# Ampli-Mic.net
KiCad netlist of a schematic drawn in EAGLE
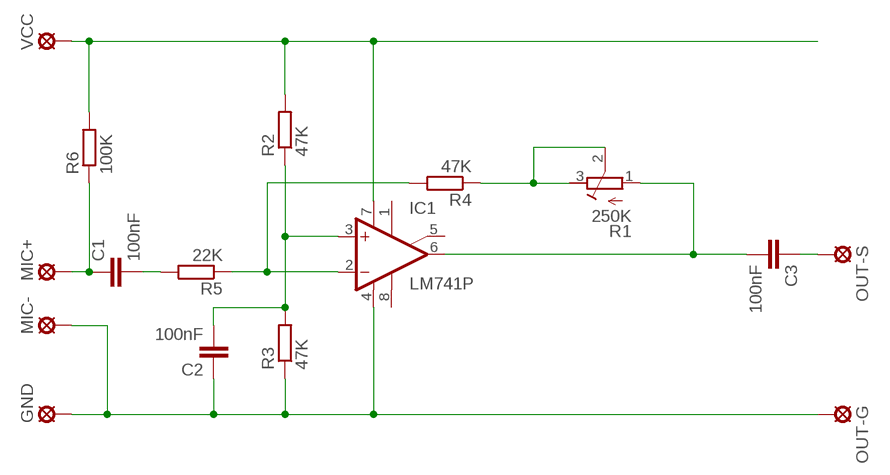
[diagram p0: schematic, sheet 1]

(export (version "E")
  (design (tool "Eeschema 10.0.6"))
  (components
    (comp (ref "C1")
      (value "100nF")
      (footprint "eagle-import:C050-024X044")
      (libsource (lib "eagle-import") (part "C-EU050-024X044"))
    )
    (comp (ref "C2")
      (value "100nF")
      (footprint "eagle-import:C050-024X044")
      (libsource (lib "eagle-import") (part "C-EU050-024X044"))
    )
    (comp (ref "C3")
      (value "100nF")
      (footprint "eagle-import:C050-024X044")
      (libsource (lib "eagle-import") (part "C-EU050-024X044"))
    )
    (comp (ref "GND")
      (value "LSP10")
      (footprint "eagle-import:LSP10")
      (libsource (lib "eagle-import") (part "LSP10"))
    )
    (comp (ref "IC1")
      (value "LM741P")
      (footprint "eagle-import:DIL08")
      (libsource (lib "eagle-import") (part "741PLM"))
    )
    (comp (ref "MIC+")
      (value "LSP10")
      (footprint "eagle-import:LSP10")
      (libsource (lib "eagle-import") (part "LSP10"))
    )
    (comp (ref "MIC-")
      (value "LSP10")
      (footprint "eagle-import:LSP10")
      (libsource (lib "eagle-import") (part "LSP10"))
    )
    (comp (ref "OUT-G")
      (value "LSP10")
      (footprint "eagle-import:LSP10")
      (libsource (lib "eagle-import") (part "LSP10"))
    )
    (comp (ref "OUT-S")
      (value "LSP10")
      (footprint "eagle-import:LSP10")
      (libsource (lib "eagle-import") (part "LSP10"))
    )
    (comp (ref "R1")
      (value "250K")
      (footprint "eagle-import:RTRIM3339P")
      (libsource (lib "eagle-import") (part "R-TRIMM3339P"))
    )
    (comp (ref "R2")
      (value "47K")
      (footprint "eagle-import:0207_10")
      (libsource (lib "eagle-import") (part "R-EU_0207/10"))
    )
    (comp (ref "R3")
      (value "47K")
      (footprint "eagle-import:0207_10")
      (libsource (lib "eagle-import") (part "R-EU_0207/10"))
    )
    (comp (ref "R4")
      (value "47K")
      (footprint "eagle-import:0207_10")
      (libsource (lib "eagle-import") (part "R-EU_0207/10"))
    )
    (comp (ref "R5")
      (value "22K")
      (footprint "eagle-import:0207_10")
      (libsource (lib "eagle-import") (part "R-EU_0207/10"))
    )
    (comp (ref "R6")
      (value "100K")
      (footprint "eagle-import:0207_10")
      (libsource (lib "eagle-import") (part "R-EU_0207/10"))
    )
    (comp (ref "VCC")
      (value "LSP10")
      (footprint "eagle-import:LSP10")
      (libsource (lib "eagle-import") (part "LSP10"))
    )
  )
  (nets
    (net (code "1") (name "Net-(C1-Pad1)") (class "Default")
      (node (ref "C1") (pin "1") (pinfunction "1_1") (pintype "passive"))
      (node (ref "MIC+") (pin "MP") (pinfunction "MP_MP") (pintype "passive"))
      (node (ref "R6") (pin "1") (pinfunction "1_1") (pintype "passive"))
    )
    (net (code "2") (name "Net-(C1-Pad2)") (class "Default")
      (node (ref "C1") (pin "2") (pinfunction "2_2") (pintype "passive"))
      (node (ref "R5") (pin "2") (pinfunction "2_2") (pintype "passive"))
    )
    (net (code "3") (name "Net-(C3-Pad1)") (class "Default")
      (node (ref "C3") (pin "1") (pinfunction "1_1") (pintype "passive"))
      (node (ref "OUT-S") (pin "MP") (pinfunction "MP_MP") (pintype "passive"))
    )
    (net (code "4") (name "Net-(IC1-+IN)") (class "Default")
      (node (ref "C2") (pin "2") (pinfunction "2_2") (pintype "passive"))
      (node (ref "IC1") (pin "3") (pinfunction "+IN_3") (pintype "input"))
      (node (ref "R2") (pin "1") (pinfunction "1_1") (pintype "passive"))
      (node (ref "R3") (pin "2") (pinfunction "2_2") (pintype "passive"))
    )
    (net (code "5") (name "Net-(IC1--IN)") (class "Default")
      (node (ref "IC1") (pin "2") (pinfunction "-IN_2") (pintype "input"))
      (node (ref "R4") (pin "2") (pinfunction "2_2") (pintype "passive"))
      (node (ref "R5") (pin "1") (pinfunction "1_1") (pintype "passive"))
    )
    (net (code "6") (name "Net-(IC1-OUT)") (class "Default")
      (node (ref "C3") (pin "2") (pinfunction "2_2") (pintype "passive"))
      (node (ref "IC1") (pin "6") (pinfunction "OUT_6") (pintype "output"))
      (node (ref "R1") (pin "1") (pinfunction "A_1") (pintype "passive"))
    )
    (net (code "7") (name "Net-(IC1-V+)") (class "Default")
      (node (ref "IC1") (pin "7") (pinfunction "V+_7") (pintype "power_in"))
      (node (ref "R2") (pin "2") (pinfunction "2_2") (pintype "passive"))
      (node (ref "R6") (pin "2") (pinfunction "2_2") (pintype "passive"))
      (node (ref "VCC") (pin "MP") (pinfunction "MP_MP") (pintype "passive"))
    )
    (net (code "8") (name "Net-(IC1-V-)") (class "Default")
      (node (ref "C2") (pin "1") (pinfunction "1_1") (pintype "passive"))
      (node (ref "GND") (pin "MP") (pinfunction "MP_MP") (pintype "passive"))
      (node (ref "IC1") (pin "4") (pinfunction "V-_4") (pintype "power_in"))
      (node (ref "MIC-") (pin "MP") (pinfunction "MP_MP") (pintype "passive"))
      (node (ref "OUT-G") (pin "MP") (pinfunction "MP_MP") (pintype "passive"))
      (node (ref "R3") (pin "1") (pinfunction "1_1") (pintype "passive"))
    )
    (net (code "9") (name "Net-(R1-E)") (class "Default")
      (node (ref "R1") (pin "2") (pinfunction "S_2") (pintype "passive"))
      (node (ref "R1") (pin "3") (pinfunction "E_3") (pintype "passive"))
      (node (ref "R4") (pin "1") (pinfunction "1_1") (pintype "passive"))
    )
    (net (code "10") (name "unconnected-(IC1-ON1-Pad1)") (class "Default")
      (node (ref "IC1") (pin "1") (pinfunction "ON1_1") (pintype "passive"))
    )
    (net (code "11") (name "unconnected-(IC1-ON2-Pad5)") (class "Default")
      (node (ref "IC1") (pin "5") (pinfunction "ON2_5") (pintype "passive"))
    )
    (net (code "12") (name "unconnected-(IC1-OPT-Pad8)") (class "Default")
      (node (ref "IC1") (pin "8") (pinfunction "OPT_8") (pintype "passive"))
    )
  )
)
